# Jetson_power.net
KiCad netlist of a schematic drawn in Altium Designer
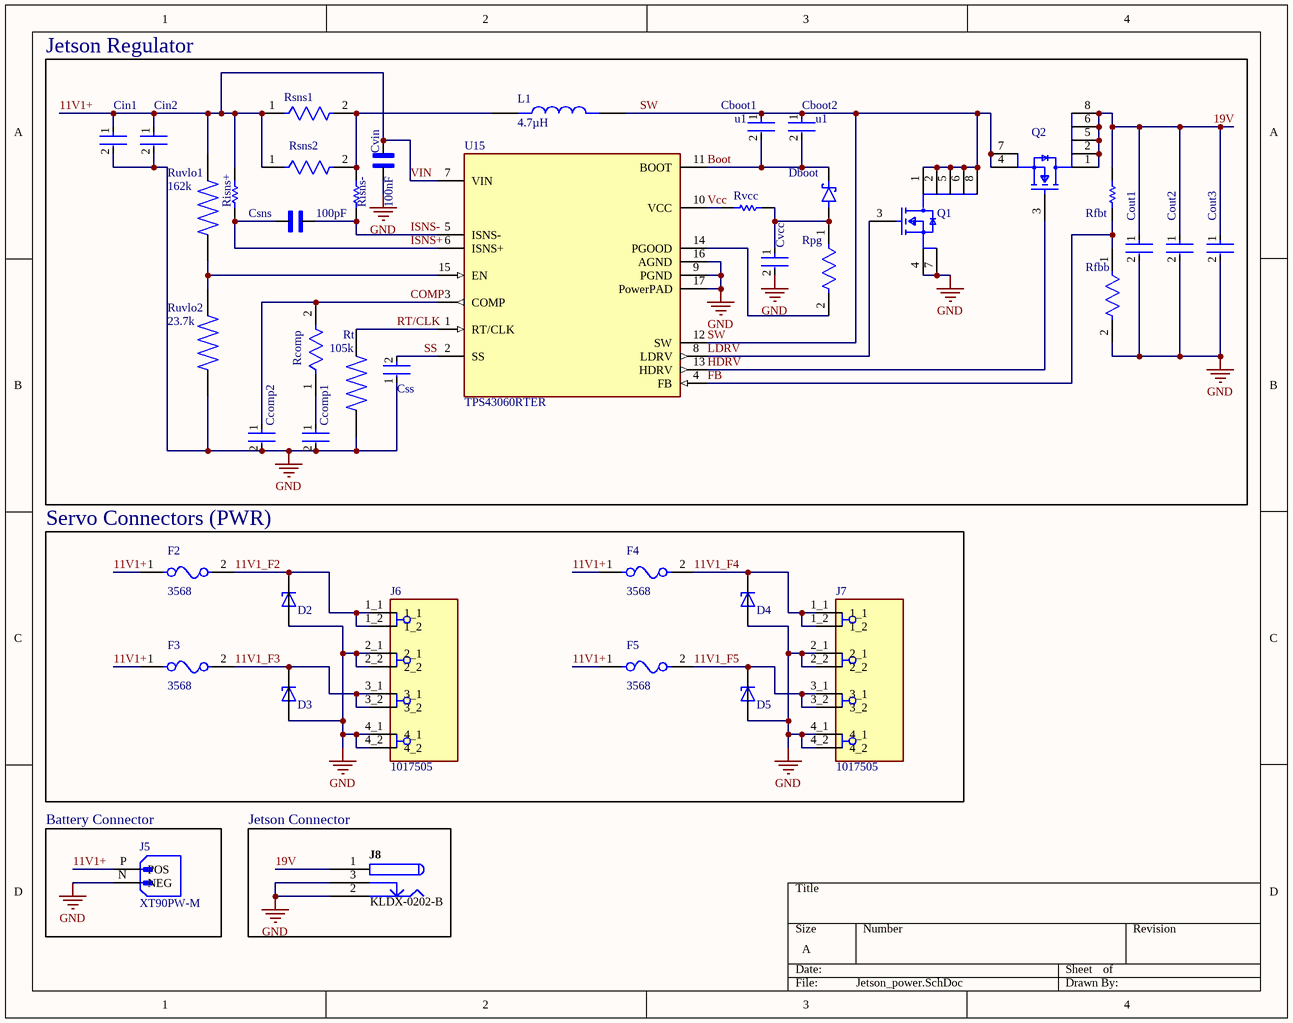
[diagram p0: Jetson_power.SchDoc]

(export (version "E")
  (design (tool "Eeschema 10.0.6"))
  (components
    (comp (ref "Cboot1")
      (value "u1")
      (footprint "FP-CC0805-0_85-MFG")
      (description "CC0805KRX7R9BB104 CAP CER 0.1UF 50V X7R 0805")
      (fields (field (name "TOLERANCE") "0.1") (field (name "MANUFACTURER PART NUMBER") "CC0805KRX7R9BB104"))
      (libsource (lib "Altium Content Vault") (part "11868f565c42a9108669ba33697ecf6"))
    )
    (comp (ref "Cboot2")
      (value "u1")
      (footprint "FP-CC0805-0_85-MFG")
      (description "CC0805KRX7R9BB104 CAP CER 0.1UF 50V X7R 0805")
      (fields (field (name "TOLERANCE") "0.1") (field (name "MANUFACTURER PART NUMBER") "CC0805KRX7R9BB104"))
      (libsource (lib "Altium Content Vault") (part "11868f565c42a9108669ba33697ecf6"))
    )
    (comp (ref "Ccomp1")
      (value "CGA4C2C0G1H822J060AA")
      (footprint "FP-CGA4J-IPC_A")
      (description "Cap Ceramic 8.2nF 50V C0G 5% Pad SMD 0805 +125°C Automotive T/R")
      (fields (field (name "TOLERANCE") "5%"))
      (libsource (lib "Altium Content Vault") (part "b4654b650e69147ec39a6b967a45e02"))
    )
    (comp (ref "Ccomp2")
      (value "GRM1555C1H391JA01J")
      (footprint "FP-GRM155-0_05-IPC_A")
      (description "Chip Multilayer Ceramic Capacitors for General Purpose, 0402, 390pF, C0G, 30ppm/°C, 5%, 50V")
      (fields (field (name "VOLTAGE") "50V") (field (name "TOLERANCE") "5%"))
      (libsource (lib "Altium Content Vault") (part "02cd4be3c70576c341d710602a673aa"))
    )
    (comp (ref "Cin1")
      (value "CL32A106KBJNNNE")
      (footprint "FP-CL32-IPC_B")
      (description "Cap Ceramic 10uF 50V X5R ±10% SMD 1210 +85°C Embossed T/R")
      (fields (field (name "TOLERANCE") "10%"))
      (libsource (lib "Altium Content Vault") (part "b4654b650e69147ec39a6b967a45e02"))
    )
    (comp (ref "Cin2")
      (value "CL32A106KBJNNNE")
      (footprint "FP-CL32-IPC_B")
      (description "Cap Ceramic 10uF 50V X5R ±10% SMD 1210 +85°C Embossed T/R")
      (fields (field (name "TOLERANCE") "10%"))
      (libsource (lib "Altium Content Vault") (part "b4654b650e69147ec39a6b967a45e02"))
    )
    (comp (ref "Cout1")
      (value "CL32B106KBJNNWE")
      (footprint "FP-CL32-IPC_B")
      (description "Cap Ceramic 10uF 50V X7R ±10% SMD 1210 +125°C Embossed T/R")
      (fields (field (name "TOLERANCE") "10%"))
      (libsource (lib "Altium Content Vault") (part "b4654b650e69147ec39a6b967a45e02"))
    )
    (comp (ref "Cout2")
      (value "CL32B106KBJNNWE")
      (footprint "FP-CL32-IPC_B")
      (description "Cap Ceramic 10uF 50V X7R ±10% SMD 1210 +125°C Embossed T/R")
      (fields (field (name "TOLERANCE") "10%"))
      (libsource (lib "Altium Content Vault") (part "b4654b650e69147ec39a6b967a45e02"))
    )
    (comp (ref "Cout3")
      (value "CL32B106KBJNNWE")
      (footprint "FP-CL32-IPC_B")
      (description "Cap Ceramic 10uF 50V X7R ±10% SMD 1210 +125°C Embossed T/R")
      (fields (field (name "TOLERANCE") "10%"))
      (libsource (lib "Altium Content Vault") (part "b4654b650e69147ec39a6b967a45e02"))
    )
    (comp (ref "Csns")
      (value "100pF")
      (footprint "CAPC1608X90N")
      (description "SMD Capacitor C0G(EIA) with Capacitance: 100pF Tol. 5%. Rated Voltage: 50Vdc")
      (fields (field (name "MF") "Murata Electronics") (field (name "MP") "GRM1885C1H101JA01D"))
      (libsource (lib "Bryan Heddle") (part "GRM1885C1H101JA01D"))
    )
    (comp (ref "Css")
      (value "C1608C0G1E472J080AA")
      (footprint "FP-C1608-080-0_1-IPC_A")
      (description "Multilayer Ceramic Capacitors 4.7nF ±5% 25V C0G SMD 0603")
      (fields (field (name "TOLERANCE") "5%"))
      (libsource (lib "Altium Content Vault") (part "236180d848d6139a670b325ea6854c9"))
    )
    (comp (ref "Cvcc")
      (value "GRM188R61C106MA73D")
      (footprint "FP-GRM188-0_2-IPC_A")
      (description "Chip Multilayer Ceramic Capacitors for General Purpose, 0603, 10uF, X5R, 15%, 20%, 16V")
      (fields (field (name "TOLERANCE") "20%") (field (name "VOLTAGE") "16V"))
      (libsource (lib "Altium Content Vault") (part "11868f565c42a9108669ba33697ecf6"))
    )
    (comp (ref "Cvin")
      (value "100nF")
      (footprint "CAPC1005X55N")
      (description "SMD Capacitor X7R(EIA) with Capacitance: 0.10uF Tol. 10%. Rated Voltage: 16Vdc")
      (fields (field (name "MP") "GRM155R71C104KA88D") (field (name "MF") "Murata"))
      (libsource (lib "Bryan Heddle") (part "GRM155R71C104KA88D"))
    )
    (comp (ref "D2")
      (value "SMBJ13A-13-F")
      (footprint "DIOM5336X250N")
      (description "400 W 13 V Uni-Directional SMT Transient Voltage Suppressor Diode - DO-214AA")
      (fields (field (name "MF") "Diodes Inc."))
      (libsource (lib "Bryan Heddle") (part "SMBJ13A-13-F"))
    )
    (comp (ref "D3")
      (value "SMBJ13A-13-F")
      (footprint "DIOM5336X250N")
      (description "400 W 13 V Uni-Directional SMT Transient Voltage Suppressor Diode - DO-214AA")
      (fields (field (name "MF") "Diodes Inc."))
      (libsource (lib "Bryan Heddle") (part "SMBJ13A-13-F"))
    )
    (comp (ref "D4")
      (value "SMBJ13A-13-F")
      (footprint "DIOM5336X250N")
      (description "400 W 13 V Uni-Directional SMT Transient Voltage Suppressor Diode - DO-214AA")
      (fields (field (name "MF") "Diodes Inc."))
      (libsource (lib "Bryan Heddle") (part "SMBJ13A-13-F"))
    )
    (comp (ref "D5")
      (value "SMBJ13A-13-F")
      (footprint "DIOM5336X250N")
      (description "400 W 13 V Uni-Directional SMT Transient Voltage Suppressor Diode - DO-214AA")
      (fields (field (name "MF") "Diodes Inc."))
      (libsource (lib "Bryan Heddle") (part "SMBJ13A-13-F"))
    )
    (comp (ref "Dboot")
      (value "XBS053V15R-G")
      (footprint "DIO_XBS053V15R-G")
      (description "Diode Schottky 20V 500mA Surface Mount SOD-523")
      (fields (field (name "MF") "Torex") (field (name "DIGI-KEY_PART_NUMBER") "XBS053V15R-G-ND"))
      (libsource (lib "Bryan Heddle") (part "XBS053V15R-G"))
    )
    (comp (ref "F2")
      (value "3568")
      (footprint "FP-3568-MFG")
      (fields (field (name "VOLTAGE") "500V"))
      (libsource (lib "Altium Content Vault") (part "3568"))
    )
    (comp (ref "F3")
      (value "3568")
      (footprint "FP-3568-MFG")
      (fields (field (name "VOLTAGE") "500V"))
      (libsource (lib "Altium Content Vault") (part "3568"))
    )
    (comp (ref "F4")
      (value "3568")
      (footprint "FP-3568-MFG")
      (fields (field (name "VOLTAGE") "500V"))
      (libsource (lib "Altium Content Vault") (part "3568"))
    )
    (comp (ref "F5")
      (value "3568")
      (footprint "FP-3568-MFG")
      (fields (field (name "VOLTAGE") "500V"))
      (libsource (lib "Altium Content Vault") (part "3568"))
    )
    (comp (ref "J5")
      (value "XT90PW-M")
      (footprint "AMASS_XT90PW-M - duplicate")
      (description "Socket; DC supply; XT90; male; PIN: 2; on PCBs; THT; Colour: yellow")
      (fields (field (name "MF") "AMASS"))
      (libsource (lib "AI_Project_Library") (part "XT90PW-M"))
    )
    (comp (ref "J6")
      (value "1017505")
      (footprint "PHOENIX_1017505")
      (fields (field (name "MF") "{'manufacturer': u'Phoenix Contact'}"))
      (libsource (lib "Bryan Heddle") (part "1017505"))
    )
    (comp (ref "J7")
      (value "1017505")
      (footprint "PHOENIX_1017505")
      (fields (field (name "MF") "{'manufacturer': u'Phoenix Contact'}"))
      (libsource (lib "Bryan Heddle") (part "1017505"))
    )
    (comp (ref "J8")
      (value "KLDX-0202-B")
      (footprint "KYCN-KLDX-0202-B_V")
      (description "3 Conductor Power Jack, 2 break 2 aux contacts")
      (libsource (lib "Altium Content Vault") (part "KYCN-KLDX-0202-B-3"))
    )
    (comp (ref "L1")
      (value "4.7µH")
      (footprint "IND_XAL6060-472MEB")
      (description "Power inductor, shielded, 20% tol, SMT, RoHS, halogen-f")
      (fields (field (name "MF") "Coilcraft") (field (name "MP") "XAL6060-472MEB"))
      (libsource (lib "Bryan Heddle") (part "XAL6060-472MEB"))
    )
    (comp (ref "Q1")
      (value "CSD17571Q2")
      (footprint "FP-DQK0006C-MFG")
      (description "MOSFET N-CH 30V 22A 6SON")
      (libsource (lib "Altium Content Vault") (part "67f8c6576a35c08c1e5776583238e4f"))
    )
    (comp (ref "Q2")
      (value "CSD17571Q2")
      (footprint "FP-DQK0006C-MFG")
      (description "MOSFET N-CH 30V 22A 6SON")
      (libsource (lib "Altium Content Vault") (part "67f8c6576a35c08c1e5776583238e4f"))
    )
    (comp (ref "Rcomp")
      (value "CRCW04025K36FKED")
      (footprint "FP-CRCW0402-e3-IPC_B")
      (description "RES Thick Film, 5.36kΩ, 1%, 0.063W, 100ppm/°C, 0402")
      (fields (field (name "TOLERANCE") "1%"))
      (libsource (lib "Altium Content Vault") (part "1029c3af85768c4190bb7ad29bc67b5"))
    )
    (comp (ref "Rfbb")
      (value "CRCW040211K0FKED")
      (footprint "FP-CRCW0402-e3-IPC_A")
      (description "RES Thick Film, 11kΩ, 1%, 0.063W, 100ppm/°C, 0402")
      (fields (field (name "TOLERANCE") "1%"))
      (libsource (lib "Altium Content Vault") (part "1029c3af85768c4190bb7ad29bc67b5"))
    )
    (comp (ref "Rfbt")
      (value "160K 1% 0603(1608)")
      (footprint "RESC0603(1608)_N")
      (description "160K 0.1W 1% 0603 (1608 Metric)  SMD")
      (fields (field (name "POWER") "0.1 W") (field (name "TOLERANCE") "1 %"))
      (libsource (lib "Altium Content Vault") (part "RES"))
    )
    (comp (ref "Risns+")
      (value "CRCW040210R0FKED")
      (footprint "RESC1005X40X25NL05T05")
      (fields (field (name "MANUFACTURER") "Vishay Dale"))
      (libsource (lib "Altium Content Vault") (part "RES"))
    )
    (comp (ref "Risns-")
      (value "CRCW040210R0FKED")
      (footprint "RESC1005X40X25NL05T05")
      (fields (field (name "MANUFACTURER") "Vishay Dale"))
      (libsource (lib "Altium Content Vault") (part "RES"))
    )
    (comp (ref "Rpg")
      (value "CRCW0402100KFKED")
      (footprint "FP-CRCW0402-e3-IPC_C")
      (description "RES Thick Film, 100kΩ, 1%, 0.063W, 100ppm/°C, 0402")
      (fields (field (name "TOLERANCE") "1%"))
      (libsource (lib "Altium Content Vault") (part "1029c3af85768c4190bb7ad29bc67b5"))
    )
    (comp (ref "Rsns1")
      (value "PRL1632-R010-F-T1")
      (footprint "FP-PRL1632-MFG")
      (description "10 mOhms ±1% 1W Chip Resistor Wide 0612 (1632 Metric), Current Sense Thin Film")
      (fields (field (name "TOLERANCE") "1%"))
      (libsource (lib "Altium Content Vault") (part "1029c3af85768c4190bb7ad29bc67b5"))
    )
    (comp (ref "Rsns2")
      (value "PRL1632-R010-F-T1")
      (footprint "FP-PRL1632-MFG")
      (description "10 mOhms ±1% 1W Chip Resistor Wide 0612 (1632 Metric), Current Sense Thin Film")
      (fields (field (name "TOLERANCE") "1%"))
      (libsource (lib "Altium Content Vault") (part "1029c3af85768c4190bb7ad29bc67b5"))
    )
    (comp (ref "Rt")
      (value "105k")
      (footprint "RESC0603X26N")
      (description "105 kOhms Â±1% 0.05W, 1/20W Chip Resistor 0201 (0603 Metric) Moisture Resistant Thick Film")
      (fields (field (name "MF") "Yageo") (field (name "MP") "RC0201FR-07105KL"))
      (libsource (lib "Bryan Heddle") (part "RC0201FR-07105KL"))
    )
    (comp (ref "Ruvlo1")
      (value "162k")
      (footprint "RESC0603X26N")
      (description "162 kOhms Â±1% 0.05W, 1/20W Chip Resistor 0201 (0603 Metric) Moisture Resistant Thick Film")
      (fields (field (name "MF") "Yageo") (field (name "MP") "RC0201FR-07162KL"))
      (libsource (lib "Bryan Heddle") (part "RC0201FR-07162KL"))
    )
    (comp (ref "Ruvlo2")
      (value "23.7k")
      (footprint "RESC0603X26N")
      (description "23.7 kOhms Â±1% 0.05W, 1/20W Chip Resistor 0201 (0603 Metric) Moisture Resistant Thick Film")
      (fields (field (name "MF") "Yageo") (field (name "MP") "RC0201FR-0723K7L"))
      (libsource (lib "Bryan Heddle") (part "RC0201FR-0723K7L"))
    )
    (comp (ref "Rvcc")
      (value "CRCW04022R00FKED")
      (footprint "RESC1005X40X25ML05T05")
      (fields (field (name "MANUFACTURER") "Vishay Dale"))
      (libsource (lib "Altium Content Vault") (part "RES"))
    )
    (comp (ref "U15")
      (value "TPS43060RTER")
      (footprint "FP-RTE0016E-IPC_B")
      (description "IC REG CTRLR BOOST 16WQFN")
      (libsource (lib "Altium Content Vault") (part "c5c4772e39b7b1cdf4ed7dbfc316528"))
    )
  )
  (nets
    (net (code "1") (name "/11V1+") (class "Default")
      (node (ref "Cin1") (pin "1") (pinfunction "1_1") (pintype "passive"))
      (node (ref "Cin2") (pin "1") (pinfunction "1_1") (pintype "passive"))
      (node (ref "Cvin") (pin "2") (pinfunction "2_2") (pintype "passive"))
      (node (ref "F2") (pin "1") (pinfunction "1_1") (pintype "passive"))
      (node (ref "F3") (pin "1") (pinfunction "1_1") (pintype "passive"))
      (node (ref "F4") (pin "1") (pinfunction "1_1") (pintype "passive"))
      (node (ref "F5") (pin "1") (pinfunction "1_1") (pintype "passive"))
      (node (ref "J5") (pin "P") (pinfunction "POS_P") (pintype "passive"))
      (node (ref "Risns+") (pin "1") (pinfunction "1_1") (pintype "passive"))
      (node (ref "Rsns1") (pin "1") (pinfunction "1_1") (pintype "passive"))
      (node (ref "Rsns2") (pin "1") (pinfunction "1_1") (pintype "passive"))
      (node (ref "Ruvlo1") (pin "2") (pinfunction "2_2") (pintype "passive"))
      (node (ref "U15") (pin "7") (pinfunction "VIN_7") (pintype "power_in"))
    )
    (net (code "2") (name "/11V1_F2") (class "Default")
      (node (ref "D2") (pin "1") (pinfunction "C_1") (pintype "passive"))
      (node (ref "F2") (pin "2") (pinfunction "2_2") (pintype "passive"))
      (node (ref "J6") (pin "1_1") (pinfunction "1_1_1_1") (pintype "passive"))
      (node (ref "J6") (pin "1_2") (pinfunction "1_2_1_2") (pintype "passive"))
    )
    (net (code "3") (name "/11V1_F3") (class "Default")
      (node (ref "D3") (pin "1") (pinfunction "C_1") (pintype "passive"))
      (node (ref "F3") (pin "2") (pinfunction "2_2") (pintype "passive"))
      (node (ref "J6") (pin "3_1") (pinfunction "3_1_3_1") (pintype "passive"))
      (node (ref "J6") (pin "3_2") (pinfunction "3_2_3_2") (pintype "passive"))
    )
    (net (code "4") (name "/11V1_F4") (class "Default")
      (node (ref "D4") (pin "1") (pinfunction "C_1") (pintype "passive"))
      (node (ref "F4") (pin "2") (pinfunction "2_2") (pintype "passive"))
      (node (ref "J7") (pin "1_1") (pinfunction "1_1_1_1") (pintype "passive"))
      (node (ref "J7") (pin "1_2") (pinfunction "1_2_1_2") (pintype "passive"))
    )
    (net (code "5") (name "/11V1_F5") (class "Default")
      (node (ref "D5") (pin "1") (pinfunction "C_1") (pintype "passive"))
      (node (ref "F5") (pin "2") (pinfunction "2_2") (pintype "passive"))
      (node (ref "J7") (pin "3_1") (pinfunction "3_1_3_1") (pintype "passive"))
      (node (ref "J7") (pin "3_2") (pinfunction "3_2_3_2") (pintype "passive"))
    )
    (net (code "6") (name "/19V") (class "Default")
      (node (ref "Cout1") (pin "1") (pinfunction "1_1") (pintype "passive"))
      (node (ref "Cout2") (pin "1") (pinfunction "1_1") (pintype "passive"))
      (node (ref "Cout3") (pin "1") (pinfunction "1_1") (pintype "passive"))
      (node (ref "J8") (pin "1") (pintype "power_in"))
      (node (ref "Q2") (pin "1") (pinfunction "D_1") (pintype "passive"))
      (node (ref "Q2") (pin "2") (pinfunction "D_2") (pintype "passive"))
      (node (ref "Q2") (pin "5") (pinfunction "D_5") (pintype "passive"))
      (node (ref "Q2") (pin "6") (pinfunction "D_6") (pintype "passive"))
      (node (ref "Q2") (pin "8") (pinfunction "D_8") (pintype "passive"))
      (node (ref "Rfbt") (pin "2") (pinfunction "2_2") (pintype "passive"))
    )
    (net (code "7") (name "/Boot") (class "Default")
      (node (ref "Cboot1") (pin "2") (pinfunction "2_2") (pintype "passive"))
      (node (ref "Cboot2") (pin "2") (pinfunction "2_2") (pintype "passive"))
      (node (ref "Dboot") (pin "C") (pinfunction "K_C") (pintype "passive"))
      (node (ref "U15") (pin "11") (pinfunction "BOOT_11") (pintype "passive"))
    )
    (net (code "8") (name "/COMP") (class "Default")
      (node (ref "Ccomp2") (pin "1") (pinfunction "1_1") (pintype "passive"))
      (node (ref "Rcomp") (pin "2") (pinfunction "2_2") (pintype "passive"))
      (node (ref "U15") (pin "3") (pinfunction "COMP_3") (pintype "output"))
    )
    (net (code "9") (name "/FB") (class "Default")
      (node (ref "Rfbb") (pin "1") (pinfunction "1_1") (pintype "passive"))
      (node (ref "Rfbt") (pin "1") (pinfunction "1_1") (pintype "passive"))
      (node (ref "U15") (pin "4") (pinfunction "FB_4") (pintype "input"))
    )
    (net (code "10") (name "/HDRV") (class "Default")
      (node (ref "Q2") (pin "3") (pinfunction "G_3") (pintype "passive"))
      (node (ref "U15") (pin "13") (pinfunction "HDRV_13") (pintype "output"))
    )
    (net (code "11") (name "/ISNS+") (class "Default")
      (node (ref "Csns") (pin "1") (pinfunction "1_1") (pintype "passive"))
      (node (ref "Risns+") (pin "2") (pinfunction "2_2") (pintype "passive"))
      (node (ref "U15") (pin "6") (pinfunction "ISNS+_6") (pintype "tri_state"))
    )
    (net (code "12") (name "/ISNS-") (class "Default")
      (node (ref "Csns") (pin "2") (pinfunction "2_2") (pintype "passive"))
      (node (ref "Risns-") (pin "1") (pinfunction "1_1") (pintype "passive"))
      (node (ref "U15") (pin "5") (pinfunction "ISNS-_5") (pintype "tri_state"))
    )
    (net (code "13") (name "/LDRV") (class "Default")
      (node (ref "Q1") (pin "3") (pinfunction "G_3") (pintype "passive"))
      (node (ref "U15") (pin "8") (pinfunction "LDRV_8") (pintype "output"))
    )
    (net (code "14") (name "/RT{slash}CLK") (class "Default")
      (node (ref "Rt") (pin "2") (pinfunction "2_2") (pintype "passive"))
      (node (ref "U15") (pin "1") (pinfunction "RT/CLK_1") (pintype "input"))
    )
    (net (code "15") (name "/SS") (class "Default")
      (node (ref "Css") (pin "2") (pinfunction "2_2") (pintype "passive"))
      (node (ref "U15") (pin "2") (pinfunction "SS_2") (pintype "passive"))
    )
    (net (code "16") (name "/SW") (class "Default")
      (node (ref "Cboot1") (pin "1") (pinfunction "1_1") (pintype "passive"))
      (node (ref "Cboot2") (pin "1") (pinfunction "1_1") (pintype "passive"))
      (node (ref "L1") (pin "2") (pinfunction "2_2") (pintype "passive"))
      (node (ref "Q1") (pin "1") (pinfunction "D_1") (pintype "passive"))
      (node (ref "Q1") (pin "2") (pinfunction "D_2") (pintype "passive"))
      (node (ref "Q1") (pin "5") (pinfunction "D_5") (pintype "passive"))
      (node (ref "Q1") (pin "6") (pinfunction "D_6") (pintype "passive"))
      (node (ref "Q1") (pin "8") (pinfunction "D_8") (pintype "passive"))
      (node (ref "Q2") (pin "4") (pinfunction "S_4") (pintype "passive"))
      (node (ref "Q2") (pin "7") (pinfunction "S_7") (pintype "passive"))
      (node (ref "U15") (pin "12") (pinfunction "SW_12") (pintype "passive"))
    )
    (net (code "17") (name "/Vcc") (class "Default")
      (node (ref "Rvcc") (pin "1") (pinfunction "1_1") (pintype "passive"))
      (node (ref "U15") (pin "10") (pinfunction "VCC_10") (pintype "power_in"))
    )
    (net (code "18") (name "GND") (class "Default")
      (node (ref "Ccomp1") (pin "2") (pinfunction "2_2") (pintype "passive"))
      (node (ref "Ccomp2") (pin "2") (pinfunction "2_2") (pintype "passive"))
      (node (ref "Cin1") (pin "2") (pinfunction "2_2") (pintype "passive"))
      (node (ref "Cin2") (pin "2") (pinfunction "2_2") (pintype "passive"))
      (node (ref "Cout1") (pin "2") (pinfunction "2_2") (pintype "passive"))
      (node (ref "Cout2") (pin "2") (pinfunction "2_2") (pintype "passive"))
      (node (ref "Cout3") (pin "2") (pinfunction "2_2") (pintype "passive"))
      (node (ref "Css") (pin "1") (pinfunction "1_1") (pintype "passive"))
      (node (ref "Cvcc") (pin "2") (pinfunction "2_2") (pintype "passive"))
      (node (ref "Cvin") (pin "1") (pinfunction "1_1") (pintype "passive"))
      (node (ref "D2") (pin "2") (pinfunction "A_2") (pintype "passive"))
      (node (ref "D3") (pin "2") (pinfunction "A_2") (pintype "passive"))
      (node (ref "D4") (pin "2") (pinfunction "A_2") (pintype "passive"))
      (node (ref "D5") (pin "2") (pinfunction "A_2") (pintype "passive"))
      (node (ref "J5") (pin "N") (pinfunction "NEG_N") (pintype "passive"))
      (node (ref "J6") (pin "2_1") (pinfunction "2_1_2_1") (pintype "passive"))
      (node (ref "J6") (pin "2_2") (pinfunction "2_2_2_2") (pintype "passive"))
      (node (ref "J6") (pin "4_1") (pinfunction "4_1_4_1") (pintype "passive"))
      (node (ref "J6") (pin "4_2") (pinfunction "4_2_4_2") (pintype "passive"))
      (node (ref "J7") (pin "2_1") (pinfunction "2_1_2_1") (pintype "passive"))
      (node (ref "J7") (pin "2_2") (pinfunction "2_2_2_2") (pintype "passive"))
      (node (ref "J7") (pin "4_1") (pinfunction "4_1_4_1") (pintype "passive"))
      (node (ref "J7") (pin "4_2") (pinfunction "4_2_4_2") (pintype "passive"))
      (node (ref "J8") (pin "2") (pintype "power_in"))
      (node (ref "J8") (pin "3") (pintype "power_in"))
      (node (ref "Q1") (pin "4") (pinfunction "S_4") (pintype "passive"))
      (node (ref "Q1") (pin "7") (pinfunction "S_7") (pintype "passive"))
      (node (ref "Rfbb") (pin "2") (pinfunction "2_2") (pintype "passive"))
      (node (ref "Rt") (pin "1") (pinfunction "1_1") (pintype "passive"))
      (node (ref "Ruvlo2") (pin "1") (pinfunction "1_1") (pintype "passive"))
      (node (ref "U15") (pin "16") (pinfunction "AGND_16") (pintype "power_in"))
      (node (ref "U15") (pin "17") (pinfunction "PowerPAD_17") (pintype "power_in"))
      (node (ref "U15") (pin "9") (pinfunction "PGND_9") (pintype "power_in"))
    )
    (net (code "19") (name "Net-(Ccomp1-Pad1)") (class "Default")
      (node (ref "Ccomp1") (pin "1") (pinfunction "1_1") (pintype "passive"))
      (node (ref "Rcomp") (pin "1") (pinfunction "1_1") (pintype "passive"))
    )
    (net (code "20") (name "Net-(Cvcc-Pad1)") (class "Default")
      (node (ref "Cvcc") (pin "1") (pinfunction "1_1") (pintype "passive"))
      (node (ref "Dboot") (pin "A") (pinfunction "A_A") (pintype "passive"))
      (node (ref "Rpg") (pin "1") (pinfunction "1_1") (pintype "passive"))
      (node (ref "Rvcc") (pin "2") (pinfunction "2_2") (pintype "passive"))
    )
    (net (code "21") (name "Net-(L1-Pad1)") (class "Default")
      (node (ref "L1") (pin "1") (pinfunction "1_1") (pintype "passive"))
      (node (ref "Risns-") (pin "2") (pinfunction "2_2") (pintype "passive"))
      (node (ref "Rsns1") (pin "2") (pinfunction "2_2") (pintype "passive"))
      (node (ref "Rsns2") (pin "2") (pinfunction "2_2") (pintype "passive"))
    )
    (net (code "22") (name "Net-(U15-EN)") (class "Default")
      (node (ref "Ruvlo1") (pin "1") (pinfunction "1_1") (pintype "passive"))
      (node (ref "Ruvlo2") (pin "2") (pinfunction "2_2") (pintype "passive"))
      (node (ref "U15") (pin "15") (pinfunction "EN_15") (pintype "input"))
    )
    (net (code "23") (name "Net-(U15-PGOOD)") (class "Default")
      (node (ref "Rpg") (pin "2") (pinfunction "2_2") (pintype "passive"))
      (node (ref "U15") (pin "14") (pinfunction "PGOOD_14") (pintype "open_collector"))
    )
  )
)
